# 1-Schematic_CessnaCitationX_CopilotBoard.net
KiCad netlist of a schematic drawn in EasyEDA
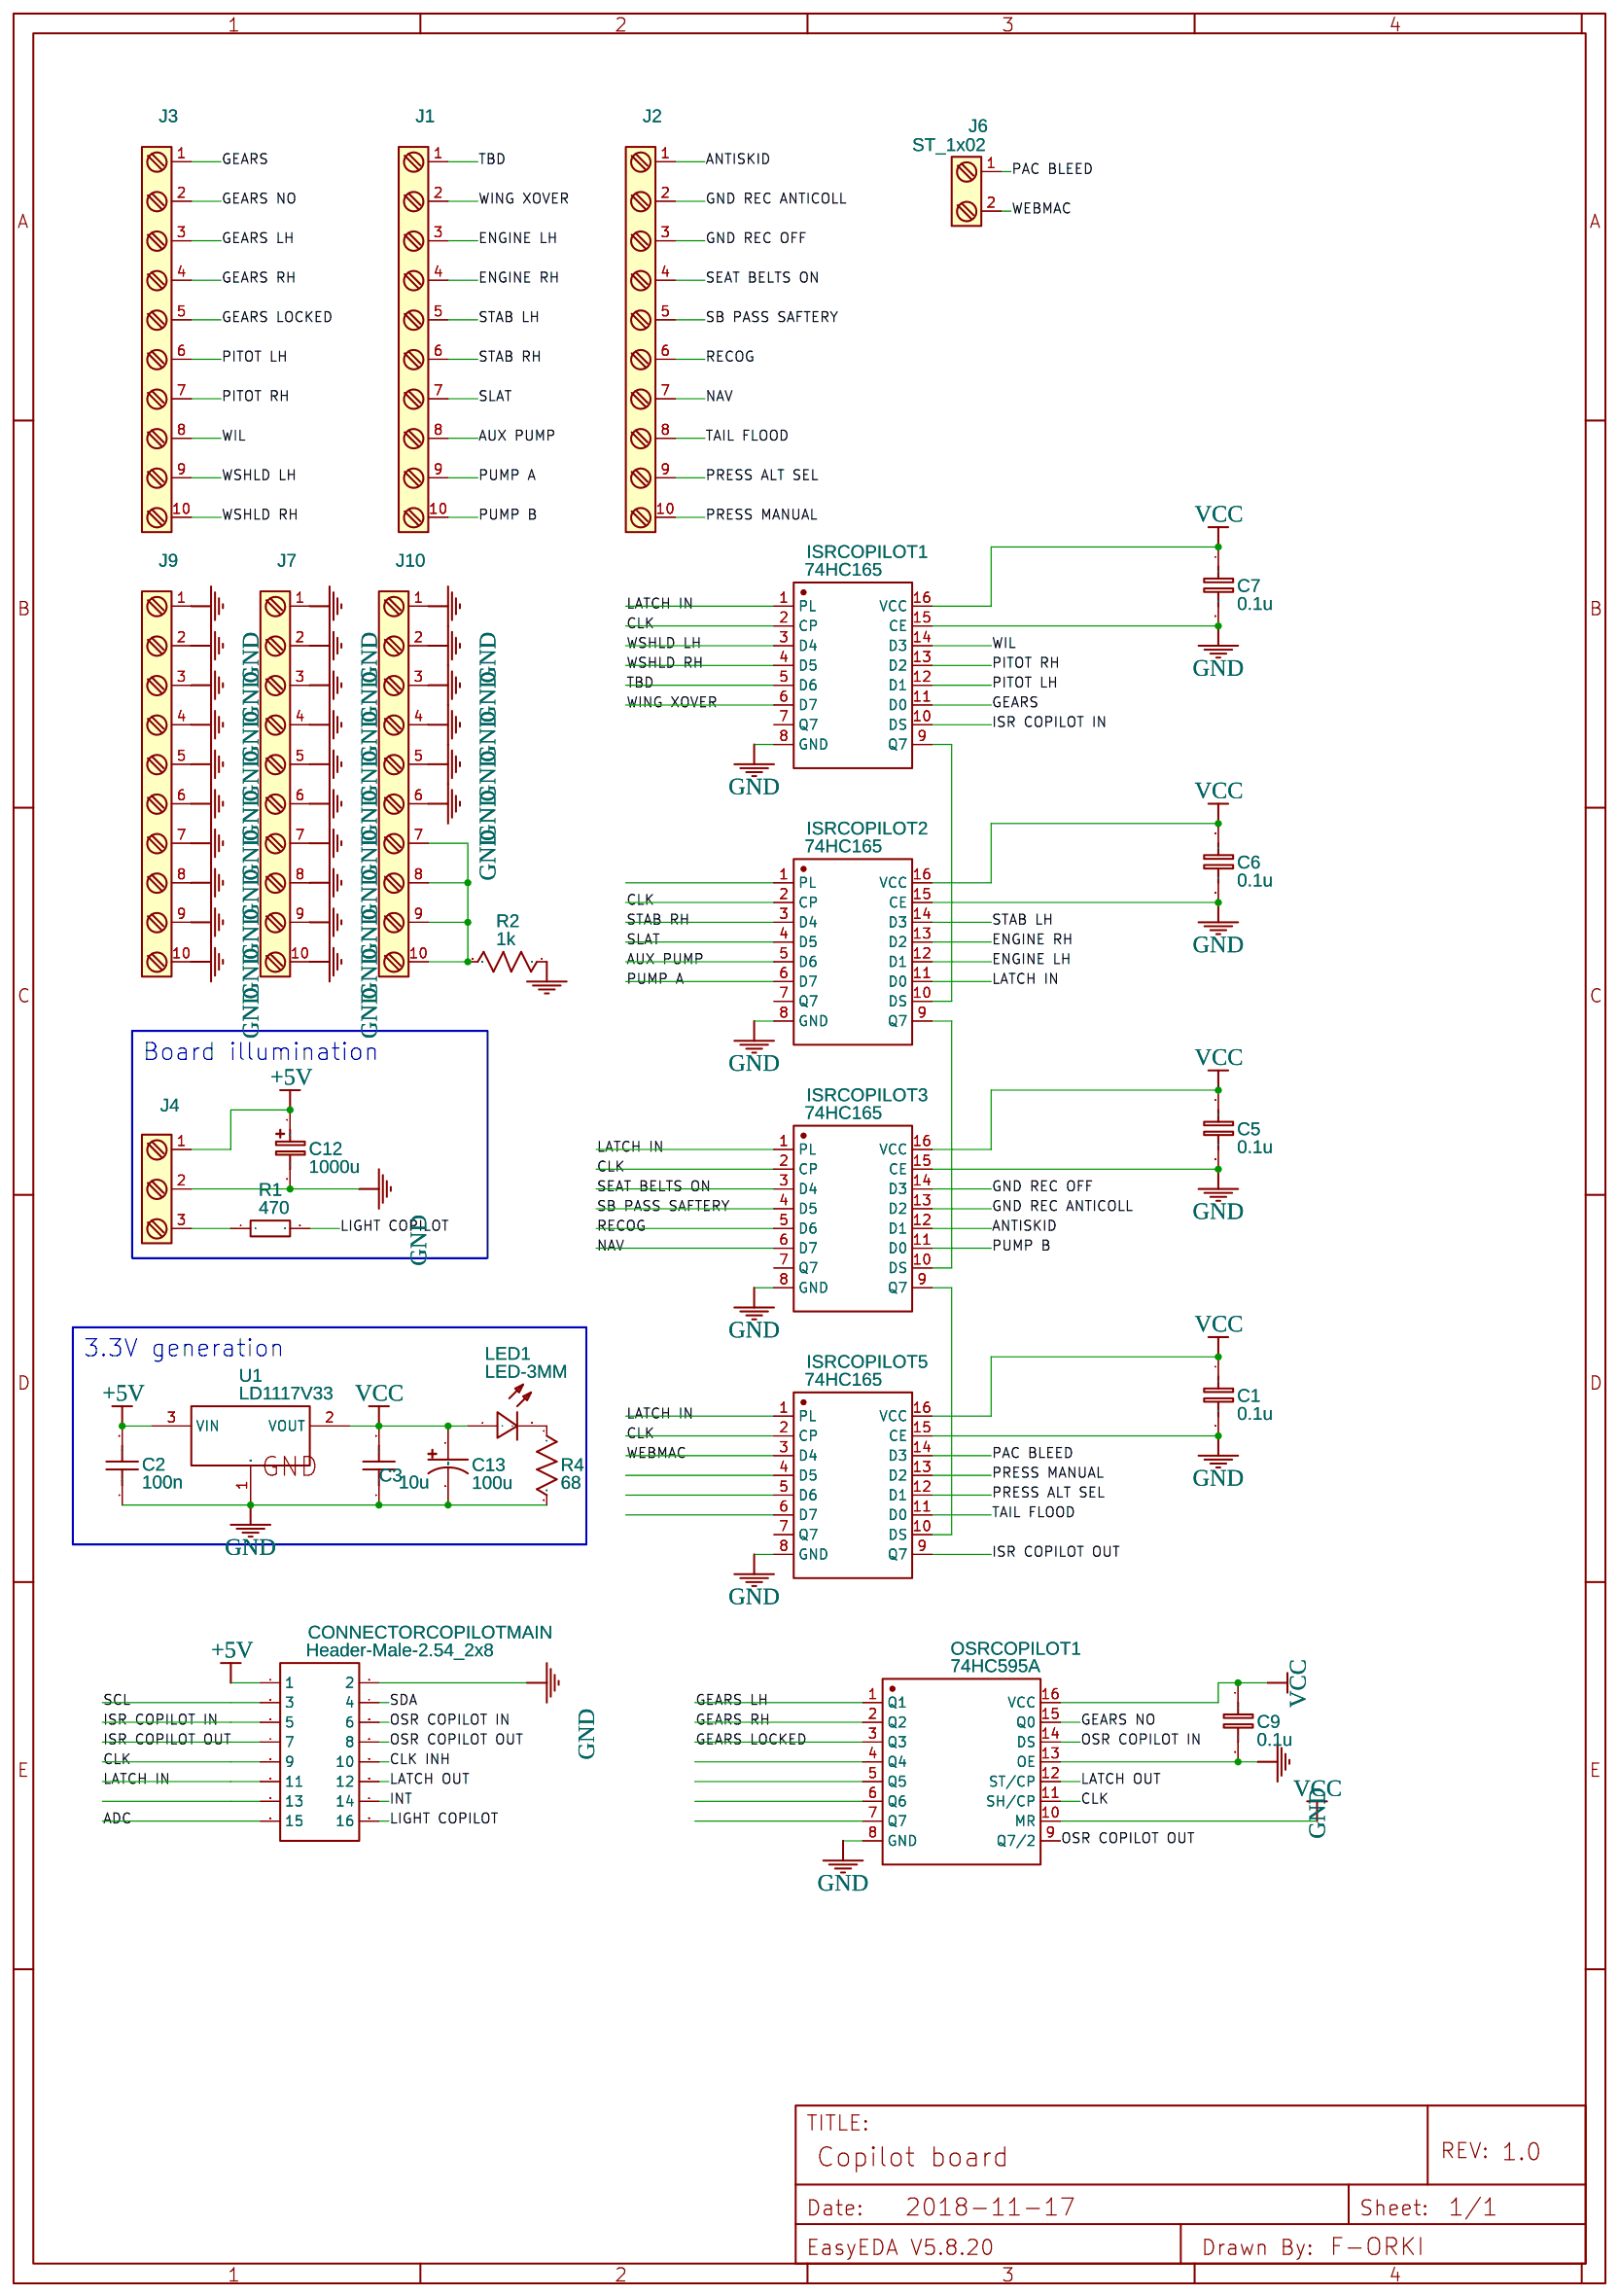
[diagram p0: schematic sheet]

(export (version "E")
  (design (tool "Eeschema 10.0.6"))
  (components
    (comp (ref "C1")
      (value "0.1u")
      (fields (field (name "BOM_Manufacturer Part") "?"))
      (libsource (lib "") (part "Cap_RAD-0.1_EU"))
    )
    (comp (ref "C2")
      (value "100n")
      (fields (field (name "BOM_Manufacturer Part") "?"))
      (libsource (lib "") (part "Cap_RAD-0.1_US"))
    )
    (comp (ref "C3")
      (value "10u")
      (fields (field (name "BOM_Manufacturer Part") "?"))
      (libsource (lib "") (part "Cap_RAD-0.1_US"))
    )
    (comp (ref "C5")
      (value "0.1u")
      (fields (field (name "BOM_Manufacturer Part") "?"))
      (libsource (lib "") (part "Cap_RAD-0.1_EU"))
    )
    (comp (ref "C6")
      (value "0.1u")
      (fields (field (name "BOM_Manufacturer Part") "?"))
      (libsource (lib "") (part "Cap_RAD-0.1_EU_1"))
    )
    (comp (ref "C7")
      (value "0.1u")
      (fields (field (name "BOM_Manufacturer Part") "?"))
      (libsource (lib "") (part "Cap_RAD-0.1_EU_1"))
    )
    (comp (ref "C9")
      (value "0.1u")
      (fields (field (name "BOM_Manufacturer Part") "?"))
      (libsource (lib "") (part "Cap_RAD-0.1_EU"))
    )
    (comp (ref "C12")
      (value "1000u")
      (fields (field (name "BOM_Manufacturer Part") "?"))
      (libsource (lib "") (part "Cap_Electrolytic(TH)_D3.0XF1.5_EU"))
    )
    (comp (ref "C13")
      (value "100u")
      (fields (field (name "BOM_Manufacturer Part") "?"))
      (libsource (lib "") (part "Cap_Electrolytic(TH)_D3.0XF1.5_US"))
    )
    (comp (ref "CONNECTORCOPILOTMAIN")
      (value "Header-Male-2.54_2x8")
      (fields
        (field (name "BOM_Manufacturer Part") "Double row straight 2*8Headers  Pins 2.54mm")
        (field (name "BOM_Supplier Part") "C68234")
      )
      (libsource (lib "") (part "Unknown_155_880"))
    )
    (comp (ref "ISRCOPILOT1")
      (value "74HC165")
      (fields
        (field (name "BOM_Manufacturer Part") "74HC165D,653")
        (field (name "BOM_Supplier Part") "C5613")
      )
      (libsource (lib "") (part "Unknown_425_290"))
    )
    (comp (ref "ISRCOPILOT2")
      (value "74HC165")
      (fields
        (field (name "BOM_Manufacturer Part") "74HC165D,653")
        (field (name "BOM_Supplier Part") "C5613")
      )
      (libsource (lib "") (part "Unknown_425_430"))
    )
    (comp (ref "ISRCOPILOT3")
      (value "74HC165")
      (fields
        (field (name "BOM_Manufacturer Part") "74HC165D,653")
        (field (name "BOM_Supplier Part") "C5613")
      )
      (libsource (lib "") (part "Unknown_425_565"))
    )
    (comp (ref "ISRCOPILOT5")
      (value "74HC165")
      (fields
        (field (name "BOM_Manufacturer Part") "74HC165D,653")
        (field (name "BOM_Supplier Part") "C5613")
      )
      (libsource (lib "") (part "Unknown_425_700"))
    )
    (comp (ref "J1")
      (value "Screw_Terminal_1x10")
      (fields (field (name "BOM_Manufacturer Part") "?"))
      (libsource (lib "") (part "Unknown_210_75"))
    )
    (comp (ref "J2")
      (value "Screw_Terminal_1x10")
      (fields (field (name "BOM_Manufacturer Part") "?"))
      (libsource (lib "") (part "Unknown_325_75"))
    )
    (comp (ref "J3")
      (value "Screw_Terminal_1x10")
      (fields (field (name "BOM_Manufacturer Part") "?"))
      (libsource (lib "") (part "Unknown_80_75"))
    )
    (comp (ref "J4")
      (value "Screw_Terminal_1x03")
      (fields (field (name "BOM_Manufacturer Part") "?"))
      (libsource (lib "") (part "Unknown_80_595"))
    )
    (comp (ref "J6")
      (value "ST_1x02")
      (fields (field (name "BOM_Manufacturer Part") "?"))
      (libsource (lib "") (part "Unknown_490_80"))
    )
    (comp (ref "J7")
      (value "Screw_Terminal_1x10")
      (fields (field (name "BOM_Manufacturer Part") "?"))
      (libsource (lib "") (part "Unknown_140_300"))
    )
    (comp (ref "J9")
      (value "Screw_Terminal_1x10")
      (fields (field (name "BOM_Manufacturer Part") "?"))
      (libsource (lib "") (part "Unknown_80_300"))
    )
    (comp (ref "J10")
      (value "Screw_Terminal_1x10")
      (fields (field (name "BOM_Manufacturer Part") "?"))
      (libsource (lib "") (part "Unknown_200_300"))
    )
    (comp (ref "LED1")
      (value "LED-3MM")
      (fields
        (field (name "BOM_Manufacturer Part") "204-10SURD/S530-A3")
        (field (name "BOM_Supplier Part") "C99772")
      )
      (libsource (lib "") (part "Unknown_250_710"))
    )
    (comp (ref "OSRCOPILOT1")
      (value "74HC595A")
      (fields (field (name "BOM_Supplier Part") "C110383"))
      (libsource (lib "") (part "Unknown_480_845"))
    )
    (comp (ref "R1")
      (value "470")
      (fields (field (name "BOM_Manufacturer Part") "?"))
      (libsource (lib "") (part "Res_AXIAL-0.3(1/8W)_EU"))
    )
    (comp (ref "R2")
      (value "1k")
      (fields (field (name "BOM_Manufacturer Part") "?"))
      (libsource (lib "") (part "Res_AXIAL-0.3(1/8W)_US"))
    )
    (comp (ref "R4")
      (value "68")
      (fields (field (name "BOM_Manufacturer Part") "?"))
      (libsource (lib "") (part "Res_AXIAL-0.3(1/8W)_US_1"))
    )
    (comp (ref "U1")
      (value "LD1117V33")
      (fields (field (name "BOM_Supplier Part") "C283467"))
      (libsource (lib "") (part "Unknown_120_735"))
    )
  )
  (nets
    (net (code "1") (name "+5V") (class "Default")
      (node (ref "C12") (pin "1") (pinfunction "1_1") (pintype "unspecified"))
      (node (ref "C2") (pin "2") (pinfunction "2_2") (pintype "unspecified"))
      (node (ref "CONNECTORCOPILOTMAIN") (pin "1") (pinfunction "1_1") (pintype "input"))
      (node (ref "J4") (pin "1") (pintype "unspecified"))
      (node (ref "U1") (pin "3") (pinfunction "VIN_3") (pintype "passive"))
    )
    (net (code "2") (name "/ADC") (class "Default")
      (node (ref "CONNECTORCOPILOTMAIN") (pin "15") (pinfunction "15_15") (pintype "input"))
    )
    (net (code "3") (name "/ANTISKID") (class "Default")
      (node (ref "ISRCOPILOT3") (pin "12") (pinfunction "D1_12") (pintype "unspecified"))
      (node (ref "J2") (pin "1") (pintype "unspecified"))
    )
    (net (code "4") (name "/AUX PUMP") (class "Default")
      (node (ref "ISRCOPILOT2") (pin "5") (pinfunction "D6_5") (pintype "unspecified"))
      (node (ref "J1") (pin "8") (pintype "unspecified"))
    )
    (net (code "5") (name "/CLK") (class "Default")
      (node (ref "CONNECTORCOPILOTMAIN") (pin "9") (pinfunction "9_9") (pintype "input"))
      (node (ref "ISRCOPILOT1") (pin "2") (pinfunction "CP_2") (pintype "unspecified"))
      (node (ref "ISRCOPILOT2") (pin "2") (pinfunction "CP_2") (pintype "unspecified"))
      (node (ref "ISRCOPILOT3") (pin "2") (pinfunction "CP_2") (pintype "unspecified"))
      (node (ref "ISRCOPILOT5") (pin "2") (pinfunction "CP_2") (pintype "unspecified"))
      (node (ref "OSRCOPILOT1") (pin "11") (pinfunction "SH/CP_11") (pintype "unspecified"))
    )
    (net (code "6") (name "/CLK INH") (class "Default")
      (node (ref "CONNECTORCOPILOTMAIN") (pin "10") (pinfunction "10_10") (pintype "input"))
    )
    (net (code "7") (name "/ENGINE LH") (class "Default")
      (node (ref "ISRCOPILOT2") (pin "12") (pinfunction "D1_12") (pintype "unspecified"))
      (node (ref "J1") (pin "3") (pintype "unspecified"))
    )
    (net (code "8") (name "/ENGINE RH") (class "Default")
      (node (ref "ISRCOPILOT2") (pin "13") (pinfunction "D2_13") (pintype "unspecified"))
      (node (ref "J1") (pin "4") (pintype "unspecified"))
    )
    (net (code "9") (name "/GEARS") (class "Default")
      (node (ref "ISRCOPILOT1") (pin "11") (pinfunction "D0_11") (pintype "unspecified"))
      (node (ref "J3") (pin "1") (pintype "unspecified"))
    )
    (net (code "10") (name "/GEARS LH") (class "Default")
      (node (ref "J3") (pin "3") (pintype "unspecified"))
      (node (ref "OSRCOPILOT1") (pin "1") (pinfunction "Q1_1") (pintype "unspecified"))
    )
    (net (code "11") (name "/GEARS LOCKED") (class "Default")
      (node (ref "J3") (pin "5") (pintype "unspecified"))
      (node (ref "OSRCOPILOT1") (pin "3") (pinfunction "Q3_3") (pintype "unspecified"))
    )
    (net (code "12") (name "/GEARS NO") (class "Default")
      (node (ref "J3") (pin "2") (pintype "unspecified"))
      (node (ref "OSRCOPILOT1") (pin "15") (pinfunction "Q0_15") (pintype "unspecified"))
    )
    (net (code "13") (name "/GEARS RH") (class "Default")
      (node (ref "J3") (pin "4") (pintype "unspecified"))
      (node (ref "OSRCOPILOT1") (pin "2") (pinfunction "Q2_2") (pintype "unspecified"))
    )
    (net (code "14") (name "/GND REC ANTICOLL") (class "Default")
      (node (ref "ISRCOPILOT3") (pin "13") (pinfunction "D2_13") (pintype "unspecified"))
      (node (ref "J2") (pin "2") (pintype "unspecified"))
    )
    (net (code "15") (name "/GND REC OFF") (class "Default")
      (node (ref "ISRCOPILOT3") (pin "14") (pinfunction "D3_14") (pintype "unspecified"))
      (node (ref "J2") (pin "3") (pintype "unspecified"))
    )
    (net (code "16") (name "/INT") (class "Default")
      (node (ref "CONNECTORCOPILOTMAIN") (pin "14") (pinfunction "14_14") (pintype "input"))
    )
    (net (code "17") (name "/ISR COPILOT IN") (class "Default")
      (node (ref "CONNECTORCOPILOTMAIN") (pin "5") (pinfunction "5_5") (pintype "input"))
      (node (ref "ISRCOPILOT1") (pin "10") (pinfunction "DS_10") (pintype "unspecified"))
    )
    (net (code "18") (name "/ISR COPILOT OUT") (class "Default")
      (node (ref "CONNECTORCOPILOTMAIN") (pin "7") (pinfunction "7_7") (pintype "input"))
      (node (ref "ISRCOPILOT5") (pin "9") (pinfunction "Q7_9") (pintype "unspecified"))
    )
    (net (code "19") (name "/LATCH IN") (class "Default")
      (node (ref "CONNECTORCOPILOTMAIN") (pin "11") (pinfunction "11_11") (pintype "input"))
      (node (ref "ISRCOPILOT1") (pin "1") (pinfunction "PL_1") (pintype "unspecified"))
      (node (ref "ISRCOPILOT2") (pin "11") (pinfunction "D0_11") (pintype "unspecified"))
      (node (ref "ISRCOPILOT3") (pin "1") (pinfunction "PL_1") (pintype "unspecified"))
      (node (ref "ISRCOPILOT5") (pin "1") (pinfunction "PL_1") (pintype "unspecified"))
    )
    (net (code "20") (name "/LATCH OUT") (class "Default")
      (node (ref "CONNECTORCOPILOTMAIN") (pin "12") (pinfunction "12_12") (pintype "input"))
      (node (ref "OSRCOPILOT1") (pin "12") (pinfunction "ST/CP_12") (pintype "unspecified"))
    )
    (net (code "21") (name "/LIGHT COPILOT") (class "Default")
      (node (ref "CONNECTORCOPILOTMAIN") (pin "16") (pinfunction "16_16") (pintype "input"))
      (node (ref "R1") (pin "2") (pinfunction "2_2") (pintype "unspecified"))
    )
    (net (code "22") (name "/NAV") (class "Default")
      (node (ref "ISRCOPILOT3") (pin "6") (pinfunction "D7_6") (pintype "unspecified"))
      (node (ref "J2") (pin "7") (pintype "unspecified"))
    )
    (net (code "23") (name "/OSR COPILOT IN") (class "Default")
      (node (ref "CONNECTORCOPILOTMAIN") (pin "6") (pinfunction "6_6") (pintype "input"))
      (node (ref "OSRCOPILOT1") (pin "14") (pinfunction "DS_14") (pintype "unspecified"))
    )
    (net (code "24") (name "/OSR COPILOT OUT") (class "Default")
      (node (ref "CONNECTORCOPILOTMAIN") (pin "8") (pinfunction "8_8") (pintype "input"))
      (node (ref "OSRCOPILOT1") (pin "9") (pinfunction "Q7/2_9") (pintype "unspecified"))
    )
    (net (code "25") (name "/PAC BLEED") (class "Default")
      (node (ref "ISRCOPILOT5") (pin "14") (pinfunction "D3_14") (pintype "unspecified"))
      (node (ref "J6") (pin "1") (pintype "unspecified"))
    )
    (net (code "26") (name "/PITOT LH") (class "Default")
      (node (ref "ISRCOPILOT1") (pin "12") (pinfunction "D1_12") (pintype "unspecified"))
      (node (ref "J3") (pin "6") (pintype "unspecified"))
    )
    (net (code "27") (name "/PITOT RH") (class "Default")
      (node (ref "ISRCOPILOT1") (pin "13") (pinfunction "D2_13") (pintype "unspecified"))
      (node (ref "J3") (pin "7") (pintype "unspecified"))
    )
    (net (code "28") (name "/PRESS ALT SEL") (class "Default")
      (node (ref "ISRCOPILOT5") (pin "12") (pinfunction "D1_12") (pintype "unspecified"))
      (node (ref "J2") (pin "9") (pintype "unspecified"))
    )
    (net (code "29") (name "/PRESS MANUAL") (class "Default")
      (node (ref "ISRCOPILOT5") (pin "13") (pinfunction "D2_13") (pintype "unspecified"))
      (node (ref "J2") (pin "10") (pintype "unspecified"))
    )
    (net (code "30") (name "/PUMP A") (class "Default")
      (node (ref "ISRCOPILOT2") (pin "6") (pinfunction "D7_6") (pintype "unspecified"))
      (node (ref "J1") (pin "9") (pintype "unspecified"))
    )
    (net (code "31") (name "/PUMP B") (class "Default")
      (node (ref "ISRCOPILOT3") (pin "11") (pinfunction "D0_11") (pintype "unspecified"))
      (node (ref "J1") (pin "10") (pintype "unspecified"))
    )
    (net (code "32") (name "/RECOG") (class "Default")
      (node (ref "ISRCOPILOT3") (pin "5") (pinfunction "D6_5") (pintype "unspecified"))
      (node (ref "J2") (pin "6") (pintype "unspecified"))
    )
    (net (code "33") (name "/SB PASS SAFTERY") (class "Default")
      (node (ref "ISRCOPILOT3") (pin "4") (pinfunction "D5_4") (pintype "unspecified"))
      (node (ref "J2") (pin "5") (pintype "unspecified"))
    )
    (net (code "34") (name "/SCL") (class "Default")
      (node (ref "CONNECTORCOPILOTMAIN") (pin "3") (pinfunction "3_3") (pintype "input"))
    )
    (net (code "35") (name "/SDA") (class "Default")
      (node (ref "CONNECTORCOPILOTMAIN") (pin "4") (pinfunction "4_4") (pintype "input"))
    )
    (net (code "36") (name "/SEAT BELTS ON") (class "Default")
      (node (ref "ISRCOPILOT3") (pin "3") (pinfunction "D4_3") (pintype "unspecified"))
      (node (ref "J2") (pin "4") (pintype "unspecified"))
    )
    (net (code "37") (name "/SLAT") (class "Default")
      (node (ref "ISRCOPILOT2") (pin "4") (pinfunction "D5_4") (pintype "unspecified"))
      (node (ref "J1") (pin "7") (pintype "unspecified"))
    )
    (net (code "38") (name "/STAB LH") (class "Default")
      (node (ref "ISRCOPILOT2") (pin "14") (pinfunction "D3_14") (pintype "unspecified"))
      (node (ref "J1") (pin "5") (pintype "unspecified"))
    )
    (net (code "39") (name "/STAB RH") (class "Default")
      (node (ref "ISRCOPILOT2") (pin "3") (pinfunction "D4_3") (pintype "unspecified"))
      (node (ref "J1") (pin "6") (pintype "unspecified"))
    )
    (net (code "40") (name "/TAIL FLOOD") (class "Default")
      (node (ref "ISRCOPILOT5") (pin "11") (pinfunction "D0_11") (pintype "unspecified"))
      (node (ref "J2") (pin "8") (pintype "unspecified"))
    )
    (net (code "41") (name "/TBD") (class "Default")
      (node (ref "ISRCOPILOT1") (pin "5") (pinfunction "D6_5") (pintype "unspecified"))
      (node (ref "J1") (pin "1") (pintype "unspecified"))
    )
    (net (code "42") (name "/WEBMAC") (class "Default")
      (node (ref "ISRCOPILOT5") (pin "3") (pinfunction "D4_3") (pintype "unspecified"))
      (node (ref "J6") (pin "2") (pintype "unspecified"))
    )
    (net (code "43") (name "/WIL") (class "Default")
      (node (ref "ISRCOPILOT1") (pin "14") (pinfunction "D3_14") (pintype "unspecified"))
      (node (ref "J3") (pin "8") (pintype "unspecified"))
    )
    (net (code "44") (name "/WING XOVER") (class "Default")
      (node (ref "ISRCOPILOT1") (pin "6") (pinfunction "D7_6") (pintype "unspecified"))
      (node (ref "J1") (pin "2") (pintype "unspecified"))
    )
    (net (code "45") (name "/WSHLD LH") (class "Default")
      (node (ref "ISRCOPILOT1") (pin "3") (pinfunction "D4_3") (pintype "unspecified"))
      (node (ref "J3") (pin "9") (pintype "unspecified"))
    )
    (net (code "46") (name "/WSHLD RH") (class "Default")
      (node (ref "ISRCOPILOT1") (pin "4") (pinfunction "D5_4") (pintype "unspecified"))
      (node (ref "J3") (pin "10") (pintype "unspecified"))
    )
    (net (code "47") (name "GND") (class "Default")
      (node (ref "C1") (pin "2") (pinfunction "2_2") (pintype "unspecified"))
      (node (ref "C12") (pin "2") (pinfunction "2_2") (pintype "unspecified"))
      (node (ref "C13") (pin "2") (pinfunction "2_2") (pintype "unspecified"))
      (node (ref "C2") (pin "1") (pinfunction "1_1") (pintype "unspecified"))
      (node (ref "C3") (pin "1") (pinfunction "1_1") (pintype "unspecified"))
      (node (ref "C5") (pin "2") (pinfunction "2_2") (pintype "unspecified"))
      (node (ref "C6") (pin "2") (pinfunction "2_2") (pintype "unspecified"))
      (node (ref "C7") (pin "2") (pinfunction "2_2") (pintype "unspecified"))
      (node (ref "C9") (pin "2") (pinfunction "2_2") (pintype "unspecified"))
      (node (ref "CONNECTORCOPILOTMAIN") (pin "2") (pinfunction "2_2") (pintype "input"))
      (node (ref "ISRCOPILOT1") (pin "15") (pinfunction "CE_15") (pintype "unspecified"))
      (node (ref "ISRCOPILOT1") (pin "8") (pinfunction "GND_8") (pintype "unspecified"))
      (node (ref "ISRCOPILOT2") (pin "15") (pinfunction "CE_15") (pintype "unspecified"))
      (node (ref "ISRCOPILOT2") (pin "8") (pinfunction "GND_8") (pintype "unspecified"))
      (node (ref "ISRCOPILOT3") (pin "15") (pinfunction "CE_15") (pintype "unspecified"))
      (node (ref "ISRCOPILOT3") (pin "8") (pinfunction "GND_8") (pintype "unspecified"))
      (node (ref "ISRCOPILOT5") (pin "15") (pinfunction "CE_15") (pintype "unspecified"))
      (node (ref "ISRCOPILOT5") (pin "8") (pinfunction "GND_8") (pintype "unspecified"))
      (node (ref "J10") (pin "1") (pintype "unspecified"))
      (node (ref "J10") (pin "2") (pintype "unspecified"))
      (node (ref "J10") (pin "3") (pintype "unspecified"))
      (node (ref "J10") (pin "4") (pintype "unspecified"))
      (node (ref "J10") (pin "5") (pintype "unspecified"))
      (node (ref "J10") (pin "6") (pintype "unspecified"))
      (node (ref "J4") (pin "2") (pintype "unspecified"))
      (node (ref "J7") (pin "1") (pintype "unspecified"))
      (node (ref "J7") (pin "10") (pintype "unspecified"))
      (node (ref "J7") (pin "2") (pintype "unspecified"))
      (node (ref "J7") (pin "3") (pintype "unspecified"))
      (node (ref "J7") (pin "4") (pintype "unspecified"))
      (node (ref "J7") (pin "5") (pintype "unspecified"))
      (node (ref "J7") (pin "6") (pintype "unspecified"))
      (node (ref "J7") (pin "7") (pintype "unspecified"))
      (node (ref "J7") (pin "8") (pintype "unspecified"))
      (node (ref "J7") (pin "9") (pintype "unspecified"))
      (node (ref "J9") (pin "1") (pintype "unspecified"))
      (node (ref "J9") (pin "10") (pintype "unspecified"))
      (node (ref "J9") (pin "2") (pintype "unspecified"))
      (node (ref "J9") (pin "3") (pintype "unspecified"))
      (node (ref "J9") (pin "4") (pintype "unspecified"))
      (node (ref "J9") (pin "5") (pintype "unspecified"))
      (node (ref "J9") (pin "6") (pintype "unspecified"))
      (node (ref "J9") (pin "7") (pintype "unspecified"))
      (node (ref "J9") (pin "8") (pintype "unspecified"))
      (node (ref "J9") (pin "9") (pintype "unspecified"))
      (node (ref "OSRCOPILOT1") (pin "13") (pinfunction "OE_13") (pintype "unspecified"))
      (node (ref "OSRCOPILOT1") (pin "8") (pinfunction "GND_8") (pintype "unspecified"))
      (node (ref "R2") (pin "1") (pinfunction "1_1") (pintype "unspecified"))
      (node (ref "R4") (pin "2") (pinfunction "2_2") (pintype "unspecified"))
      (node (ref "U1") (pin "1") (pinfunction "GND_1") (pintype "unspecified"))
    )
    (net (code "48") (name "Net-(ISRCOPILOT2-DS)") (class "Default")
      (node (ref "ISRCOPILOT1") (pin "9") (pinfunction "Q7_9") (pintype "unspecified"))
      (node (ref "ISRCOPILOT2") (pin "10") (pinfunction "DS_10") (pintype "unspecified"))
    )
    (net (code "49") (name "Net-(ISRCOPILOT3-DS)") (class "Default")
      (node (ref "ISRCOPILOT2") (pin "9") (pinfunction "Q7_9") (pintype "unspecified"))
      (node (ref "ISRCOPILOT3") (pin "10") (pinfunction "DS_10") (pintype "unspecified"))
    )
    (net (code "50") (name "Net-(ISRCOPILOT5-DS)") (class "Default")
      (node (ref "ISRCOPILOT3") (pin "9") (pinfunction "Q7_9") (pintype "unspecified"))
      (node (ref "ISRCOPILOT5") (pin "10") (pinfunction "DS_10") (pintype "unspecified"))
    )
    (net (code "51") (name "Net-(J4-Pad3)") (class "Default")
      (node (ref "J4") (pin "3") (pintype "unspecified"))
      (node (ref "R1") (pin "1") (pinfunction "1_1") (pintype "unspecified"))
    )
    (net (code "52") (name "Net-(J10-Pad10)") (class "Default")
      (node (ref "J10") (pin "10") (pintype "unspecified"))
      (node (ref "J10") (pin "7") (pintype "unspecified"))
      (node (ref "J10") (pin "8") (pintype "unspecified"))
      (node (ref "J10") (pin "9") (pintype "unspecified"))
      (node (ref "R2") (pin "2") (pinfunction "2_2") (pintype "unspecified"))
    )
    (net (code "53") (name "Net-(LED1--)") (class "Default")
      (node (ref "LED1") (pin "2") (pinfunction "-_2") (pintype "unspecified"))
      (node (ref "R4") (pin "1") (pinfunction "1_1") (pintype "unspecified"))
    )
    (net (code "54") (name "VCC") (class "Default")
      (node (ref "C1") (pin "1") (pinfunction "1_1") (pintype "unspecified"))
      (node (ref "C13") (pin "1") (pinfunction "1_1") (pintype "unspecified"))
      (node (ref "C3") (pin "2") (pinfunction "2_2") (pintype "unspecified"))
      (node (ref "C5") (pin "1") (pinfunction "1_1") (pintype "unspecified"))
      (node (ref "C6") (pin "1") (pinfunction "1_1") (pintype "unspecified"))
      (node (ref "C7") (pin "1") (pinfunction "1_1") (pintype "unspecified"))
      (node (ref "C9") (pin "1") (pinfunction "1_1") (pintype "unspecified"))
      (node (ref "ISRCOPILOT1") (pin "16") (pinfunction "VCC_16") (pintype "unspecified"))
      (node (ref "ISRCOPILOT2") (pin "16") (pinfunction "VCC_16") (pintype "unspecified"))
      (node (ref "ISRCOPILOT3") (pin "16") (pinfunction "VCC_16") (pintype "unspecified"))
      (node (ref "ISRCOPILOT5") (pin "16") (pinfunction "VCC_16") (pintype "unspecified"))
      (node (ref "LED1") (pin "1") (pinfunction "+_1") (pintype "unspecified"))
      (node (ref "OSRCOPILOT1") (pin "10") (pinfunction "MR_10") (pintype "unspecified"))
      (node (ref "OSRCOPILOT1") (pin "16") (pinfunction "VCC_16") (pintype "unspecified"))
      (node (ref "U1") (pin "2") (pinfunction "VOUT_2") (pintype "passive"))
    )
    (net (code "55") (name "unconnected-(CONNECTORCOPILOTMAIN-Pad13)") (class "Default")
      (node (ref "CONNECTORCOPILOTMAIN") (pin "13") (pinfunction "13_13") (pintype "input"))
    )
    (net (code "56") (name "unconnected-(ISRCOPILOT1-Q7-Pad7)") (class "Default")
      (node (ref "ISRCOPILOT1") (pin "7") (pinfunction "Q7_7") (pintype "unspecified"))
    )
    (net (code "57") (name "unconnected-(ISRCOPILOT2-PL-Pad1)") (class "Default")
      (node (ref "ISRCOPILOT2") (pin "1") (pinfunction "PL_1") (pintype "unspecified"))
    )
    (net (code "58") (name "unconnected-(ISRCOPILOT2-Q7-Pad7)") (class "Default")
      (node (ref "ISRCOPILOT2") (pin "7") (pinfunction "Q7_7") (pintype "unspecified"))
    )
    (net (code "59") (name "unconnected-(ISRCOPILOT3-Q7-Pad7)") (class "Default")
      (node (ref "ISRCOPILOT3") (pin "7") (pinfunction "Q7_7") (pintype "unspecified"))
    )
    (net (code "60") (name "unconnected-(ISRCOPILOT5-D5-Pad4)") (class "Default")
      (node (ref "ISRCOPILOT5") (pin "4") (pinfunction "D5_4") (pintype "unspecified"))
    )
    (net (code "61") (name "unconnected-(ISRCOPILOT5-D6-Pad5)") (class "Default")
      (node (ref "ISRCOPILOT5") (pin "5") (pinfunction "D6_5") (pintype "unspecified"))
    )
    (net (code "62") (name "unconnected-(ISRCOPILOT5-D7-Pad6)") (class "Default")
      (node (ref "ISRCOPILOT5") (pin "6") (pinfunction "D7_6") (pintype "unspecified"))
    )
    (net (code "63") (name "unconnected-(ISRCOPILOT5-Q7-Pad7)") (class "Default")
      (node (ref "ISRCOPILOT5") (pin "7") (pinfunction "Q7_7") (pintype "unspecified"))
    )
    (net (code "64") (name "unconnected-(OSRCOPILOT1-Q4-Pad4)") (class "Default")
      (node (ref "OSRCOPILOT1") (pin "4") (pinfunction "Q4_4") (pintype "unspecified"))
    )
    (net (code "65") (name "unconnected-(OSRCOPILOT1-Q5-Pad5)") (class "Default")
      (node (ref "OSRCOPILOT1") (pin "5") (pinfunction "Q5_5") (pintype "unspecified"))
    )
    (net (code "66") (name "unconnected-(OSRCOPILOT1-Q6-Pad6)") (class "Default")
      (node (ref "OSRCOPILOT1") (pin "6") (pinfunction "Q6_6") (pintype "unspecified"))
    )
    (net (code "67") (name "unconnected-(OSRCOPILOT1-Q7-Pad7)") (class "Default")
      (node (ref "OSRCOPILOT1") (pin "7") (pinfunction "Q7_7") (pintype "unspecified"))
    )
  )
)
